# Ethylene_Sensor_Rev2.net
KiCad netlist of a schematic drawn in Altium Designer
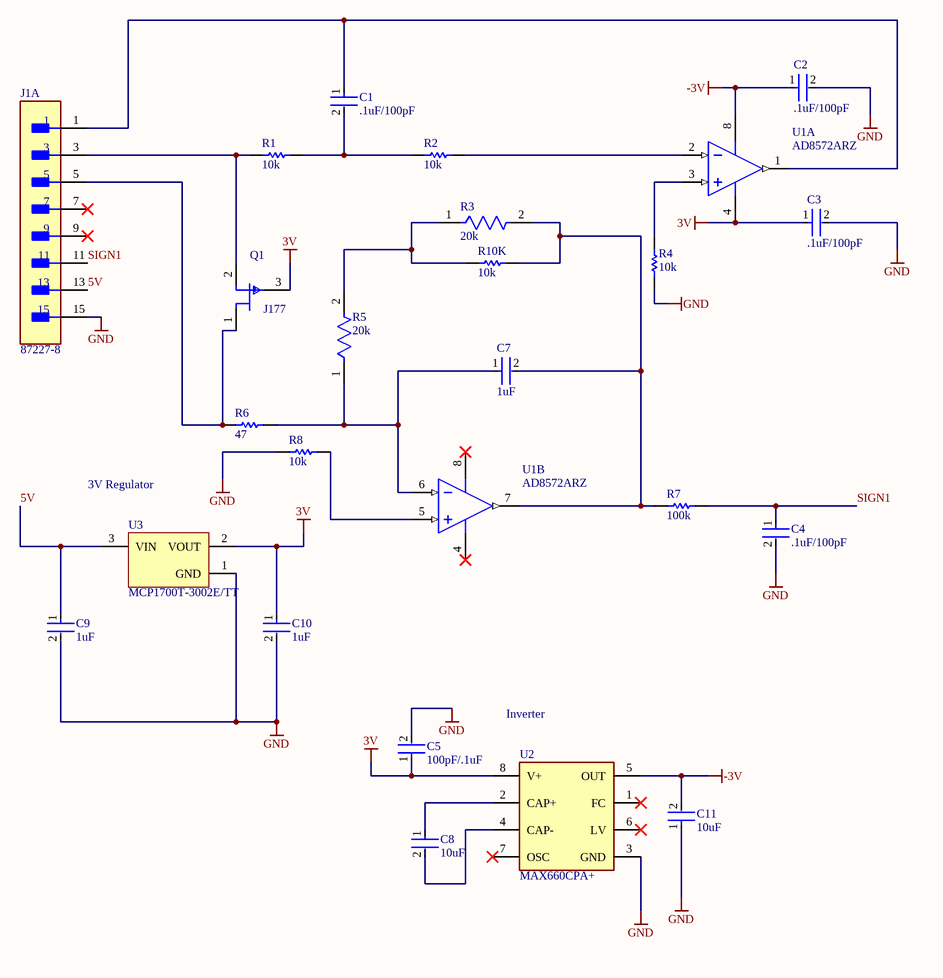
[diagram p0: Ethylene Sensor Rev2.SchDoc]

(export (version "E")
  (design (tool "Eeschema 10.0.6"))
  (components
    (comp (ref "C1")
      (value ".1uF/100pF")
      (footprint "FP-RCE0K1-MFG")
      (description "Cap Ceramic 100pF 100V C0G ±5% Radial 5mm +125°C Automotive Bulk")
      (fields (field (name "TOLERANCE") "5%"))
      (libsource (lib "Altium Content Vault") (part "b4654b650e69147ec39a6b967a45e02"))
    )
    (comp (ref "C2")
      (value ".1uF/100pF")
      (footprint "FP-RCE0K1-MFG")
      (description "Cap Ceramic 100pF 100V C0G ±5% Radial 5mm +125°C Automotive Bulk")
      (fields (field (name "TOLERANCE") "5%"))
      (libsource (lib "Altium Content Vault") (part "b4654b650e69147ec39a6b967a45e02"))
    )
    (comp (ref "C3")
      (value ".1uF/100pF")
      (footprint "FP-RCE0K1-MFG")
      (description "Cap Ceramic 100pF 100V C0G ±5% Radial 5mm +125°C Automotive Bulk")
      (fields (field (name "TOLERANCE") "5%"))
      (libsource (lib "Altium Content Vault") (part "b4654b650e69147ec39a6b967a45e02"))
    )
    (comp (ref "C4")
      (value ".1uF/100pF")
      (footprint "FP-RCE0K1-MFG")
      (description "Cap Ceramic 100pF 100V C0G ±5% Radial 5mm +125°C Automotive Bulk")
      (fields (field (name "TOLERANCE") "5%"))
      (libsource (lib "Altium Content Vault") (part "b4654b650e69147ec39a6b967a45e02"))
    )
    (comp (ref "C5")
      (value "100pF/.1uF")
      (footprint "FP-RCE0DB-MFG")
      (description "Cap Ceramic 100pF 100V C0G ±5% Radial 2.5mm +125°C Ammo Pack")
      (fields (field (name "TOLERANCE") "5%"))
      (libsource (lib "Altium Content Vault") (part "b4654b650e69147ec39a6b967a45e02"))
    )
    (comp (ref "C7")
      (value "1uF")
      (footprint "FP-K105Z20Y5VF5TL2-MFG")
      (description "CAP CER 1UF 50V Y5V RADIAL")
      (fields
        (field (name "TOLERANCE") "-20+80%")
        (field (name "OCTOPART") "https://octopart.com/k105z20y5vf5tl2-vishay-39475252")
      )
      (libsource (lib "Altium Content Vault") (part "11868f565c42a9108669ba33697ecf6"))
    )
    (comp (ref "C8")
      (value "10uF")
      (footprint "FP-RCE3M1-MFG")
      (description "Cap Ceramic 10uF 25V X7R ±10% Radial 5mm +125°C Automotive Ammo Pack")
      (fields (field (name "TOLERANCE") "10%"))
      (libsource (lib "Altium Content Vault") (part "02cd4be3c70576c341d710602a673aa"))
    )
    (comp (ref "C9")
      (value "1uF")
      (footprint "FP-K105Z20Y5VF5TL2-MFG")
      (description "CAP CER 1UF 50V Y5V RADIAL")
      (fields
        (field (name "TOLERANCE") "-20+80%")
        (field (name "OCTOPART") "https://octopart.com/k105z20y5vf5tl2-vishay-39475252")
      )
      (libsource (lib "Altium Content Vault") (part "11868f565c42a9108669ba33697ecf6"))
    )
    (comp (ref "C10")
      (value "1uF")
      (footprint "FP-K105Z20Y5VF5TL2-MFG")
      (description "CAP CER 1UF 50V Y5V RADIAL")
      (fields
        (field (name "TOLERANCE") "-20+80%")
        (field (name "OCTOPART") "https://octopart.com/k105z20y5vf5tl2-vishay-39475252")
      )
      (libsource (lib "Altium Content Vault") (part "11868f565c42a9108669ba33697ecf6"))
    )
    (comp (ref "C11")
      (value "10uF")
      (footprint "FP-RCE3M1-MFG")
      (description "Cap Ceramic 10uF 25V X7R ±10% Radial 5mm +125°C Automotive Ammo Pack")
      (fields (field (name "TOLERANCE") "10%"))
      (libsource (lib "Altium Content Vault") (part "02cd4be3c70576c341d710602a673aa"))
    )
    (comp (ref "J1")
      (value "87227-8")
      (footprint "FP-87227-8-MFG")
      (description "CONN HEADER VERT 16POS 2.54MM")
      (fields
        (field (name "MANUFACTURER") "TE Connectivity")
        (field (name "OCTOPART") "https://octopart.com/87227-8-te+connectivity-39407754")
      )
      (libsource (lib "Altium Content Vault") (part "4b6d22b45e2f925f038cba5d936fbcc"))
    )
    (comp (ref "Q1")
      (value "J177")
      (footprint "FP-318-08-IPC_C")
      (description "JFET P-CH 30V 0.225W SOT23")
      (libsource (lib "Altium Content Vault") (part "f35b6042eff1b6cb0a0a26375b7670e"))
    )
    (comp (ref "R1")
      (value "10k")
      (footprint "OMTE-RES7X2.5-2")
      (fields
        (field (name "TOLERANCE") "±5%")
        (field (name "PARTNUMBER") "OD103JE")
        (field (name "MANUFACTURER") "Ohmite")
      )
      (libsource (lib "Altium Content Vault") (part "RES-2"))
    )
    (comp (ref "R2")
      (value "10k")
      (footprint "OMTE-RES7X2.5-2")
      (fields
        (field (name "TOLERANCE") "±5%")
        (field (name "PARTNUMBER") "OD103JE")
        (field (name "MANUFACTURER") "Ohmite")
      )
      (libsource (lib "Altium Content Vault") (part "RES-2"))
    )
    (comp (ref "R3")
      (value "20k")
      (footprint "FP-S102K-MFG")
      (description "RES 20K OHM 0.6W 0.01% RADIAL")
      (fields (field (name "TOLERANCE") "0.01%"))
      (libsource (lib "Altium Content Vault") (part "1029c3af85768c4190bb7ad29bc67b5"))
    )
    (comp (ref "R4")
      (value "10k")
      (footprint "OMTE-RES7X2.5-2")
      (fields
        (field (name "TOLERANCE") "±5%")
        (field (name "PARTNUMBER") "OD103JE")
        (field (name "MANUFACTURER") "Ohmite")
      )
      (libsource (lib "Altium Content Vault") (part "RES-2"))
    )
    (comp (ref "R5")
      (value "20k")
      (footprint "FP-S102K-MFG")
      (description "RES 20K OHM 0.6W 0.01% RADIAL")
      (fields (field (name "TOLERANCE") "0.01%"))
      (libsource (lib "Altium Content Vault") (part "1029c3af85768c4190bb7ad29bc67b5"))
    )
    (comp (ref "R6")
      (value "47")
      (footprint "RESC1609X50X30LL10T20")
      (fields (field (name "MANUFACTURER") "Vishay Dale") (field (name "PART NUMBER") "CRCW060347R0FKEA"))
      (libsource (lib "Altium Content Vault") (part "RES"))
    )
    (comp (ref "R7")
      (value "100k")
      (footprint "RESA60-630X240")
      (description "Axial Resistor, 100 KOhm, +/- 1%, 0.25 W, -55 to 155 degC, 2-Pin THD, RoHS, Bulk")
      (fields (field (name "TOLERANCE") "1%"))
      (libsource (lib "Altium Content Vault") (part "RES-2"))
    )
    (comp (ref "R8")
      (value "10k")
      (footprint "OMTE-RES7X2.5-2")
      (fields
        (field (name "TOLERANCE") "±5%")
        (field (name "PARTNUMBER") "OD103JE")
        (field (name "MANUFACTURER") "Ohmite")
      )
      (libsource (lib "Altium Content Vault") (part "RES-2"))
    )
    (comp (ref "R10K")
      (value "10k")
      (footprint "OMTE-RES7X2.5-2")
      (fields
        (field (name "TOLERANCE") "±5%")
        (field (name "PARTNUMBER") "OD103JE")
        (field (name "MANUFACTURER") "Ohmite")
      )
      (libsource (lib "Altium Content Vault") (part "RES-2"))
    )
    (comp (ref "U1")
      (value "AD8572ARZ")
      (footprint "ADI-R-8_L")
      (fields (field (name "MANUFACTURER") "Analog Devices") (field (name "GENERIC PART NUMBER") "AD8572"))
      (libsource (lib "Altium Content Vault") (part "ADI-OP29X-R-8"))
    )
    (comp (ref "U2")
      (value "MAX660CPA+")
      (footprint "FP-P8-2-MFG")
      (description "IC REG CHARG PUMP INV 100MA 8DIP")
      (fields
        (field (name "OCTOPART") "https://octopart.com/max660cpa%2B-maxim+integrated-39427913")
        (field (name "MANUFACTURER") "Maxim Integrated")
      )
      (libsource (lib "Altium Content Vault") (part "cb4f88f8f8861f0afe4fdc40404f196"))
    )
    (comp (ref "U3")
      (value "MCP1700T-3002E/TT")
      (footprint "SOT-23-TT3_L")
      (description "Low Quiescent Current LDO, 3-Pin SOT-23, Extended Temperature, Tape and Reel")
      (libsource (lib "Altium Content Vault") (part "PM-LINEREG-MCP1700-IL3"))
    )
  )
  (nets
    (net (code "1") (name "-3V") (class "Default")
      (node (ref "C11") (pin "2") (pinfunction "2_2") (pintype "passive"))
      (node (ref "C2") (pin "1") (pinfunction "1_1") (pintype "passive"))
      (node (ref "U1") (pin "8") (pinfunction "+V_8") (pintype "power_in"))
      (node (ref "U2") (pin "5") (pinfunction "OUT_5") (pintype "power_in"))
    )
    (net (code "2") (name "/5V") (class "Default")
      (node (ref "C9") (pin "1") (pinfunction "1_1") (pintype "passive"))
      (node (ref "J1") (pin "13") (pinfunction "13_13") (pintype "passive"))
      (node (ref "U3") (pin "3") (pinfunction "VIN_3") (pintype "power_in"))
    )
    (net (code "3") (name "/SIGN1") (class "Default")
      (node (ref "C4") (pin "1") (pinfunction "1_1") (pintype "passive"))
      (node (ref "J1") (pin "11") (pinfunction "11_11") (pintype "passive"))
      (node (ref "R7") (pin "2") (pinfunction "2_2") (pintype "passive"))
    )
    (net (code "4") (name "3V") (class "Default")
      (node (ref "C10") (pin "1") (pinfunction "1_1") (pintype "passive"))
      (node (ref "C3") (pin "1") (pinfunction "1_1") (pintype "passive"))
      (node (ref "C5") (pin "1") (pinfunction "1_1") (pintype "passive"))
      (node (ref "Q1") (pin "3") (pinfunction "G_3") (pintype "passive"))
      (node (ref "U1") (pin "4") (pinfunction "-V_4") (pintype "power_in"))
      (node (ref "U2") (pin "8") (pinfunction "V+_8") (pintype "power_in"))
      (node (ref "U3") (pin "2") (pinfunction "VOUT_2") (pintype "power_in"))
    )
    (net (code "5") (name "GND") (class "Default")
      (node (ref "C10") (pin "2") (pinfunction "2_2") (pintype "passive"))
      (node (ref "C11") (pin "1") (pinfunction "1_1") (pintype "passive"))
      (node (ref "C2") (pin "2") (pinfunction "2_2") (pintype "passive"))
      (node (ref "C3") (pin "2") (pinfunction "2_2") (pintype "passive"))
      (node (ref "C4") (pin "2") (pinfunction "2_2") (pintype "passive"))
      (node (ref "C5") (pin "2") (pinfunction "2_2") (pintype "passive"))
      (node (ref "C9") (pin "2") (pinfunction "2_2") (pintype "passive"))
      (node (ref "J1") (pin "15") (pinfunction "15_15") (pintype "passive"))
      (node (ref "R4") (pin "1") (pinfunction "1_1") (pintype "passive"))
      (node (ref "R8") (pin "1") (pinfunction "1_1") (pintype "passive"))
      (node (ref "U2") (pin "3") (pinfunction "GND_3") (pintype "power_in"))
      (node (ref "U3") (pin "1") (pinfunction "GND_1") (pintype "power_in"))
    )
    (net (code "6") (name "Net-(C1-Pad2)") (class "Default")
      (node (ref "C1") (pin "2") (pinfunction "2_2") (pintype "passive"))
      (node (ref "R1") (pin "2") (pinfunction "2_2") (pintype "passive"))
      (node (ref "R2") (pin "1") (pinfunction "1_1") (pintype "passive"))
    )
    (net (code "7") (name "Net-(Q1-D)") (class "Default")
      (node (ref "J1") (pin "5") (pinfunction "5_5") (pintype "passive"))
      (node (ref "Q1") (pin "1") (pinfunction "D_1") (pintype "passive"))
      (node (ref "R6") (pin "1") (pinfunction "1_1") (pintype "passive"))
    )
    (net (code "8") (name "Net-(Q1-S)") (class "Default")
      (node (ref "J1") (pin "3") (pinfunction "3_3") (pintype "passive"))
      (node (ref "Q1") (pin "2") (pinfunction "S_2") (pintype "passive"))
      (node (ref "R1") (pin "1") (pinfunction "1_1") (pintype "passive"))
    )
    (net (code "9") (name "Net-(R10K-Pad1)") (class "Default")
      (node (ref "R10K") (pin "1") (pinfunction "1_1") (pintype "passive"))
      (node (ref "R3") (pin "1") (pinfunction "1_1") (pintype "passive"))
      (node (ref "R5") (pin "2") (pinfunction "2_2") (pintype "passive"))
    )
    (net (code "10") (name "Net-(U1A-+IN_A)") (class "Default")
      (node (ref "R4") (pin "2") (pinfunction "2_2") (pintype "passive"))
      (node (ref "U1") (pin "3") (pinfunction "+IN_A_3") (pintype "input"))
    )
    (net (code "11") (name "Net-(U1A--IN_A)") (class "Default")
      (node (ref "R2") (pin "2") (pinfunction "2_2") (pintype "passive"))
      (node (ref "U1") (pin "2") (pinfunction "-IN_A_2") (pintype "input"))
    )
    (net (code "12") (name "Net-(U1A-OUT_A)") (class "Default")
      (node (ref "C1") (pin "1") (pinfunction "1_1") (pintype "passive"))
      (node (ref "J1") (pin "1") (pinfunction "1_1") (pintype "passive"))
      (node (ref "U1") (pin "1") (pinfunction "OUT_A_1") (pintype "output"))
    )
    (net (code "13") (name "Net-(U1B-+IN_B)") (class "Default")
      (node (ref "R8") (pin "2") (pinfunction "2_2") (pintype "passive"))
      (node (ref "U1") (pin "5") (pinfunction "+IN_B_5") (pintype "input"))
    )
    (net (code "14") (name "Net-(U1B--IN_B)") (class "Default")
      (node (ref "C7") (pin "1") (pinfunction "1_1") (pintype "passive"))
      (node (ref "R5") (pin "1") (pinfunction "1_1") (pintype "passive"))
      (node (ref "R6") (pin "2") (pinfunction "2_2") (pintype "passive"))
      (node (ref "U1") (pin "6") (pinfunction "-IN_B_6") (pintype "input"))
    )
    (net (code "15") (name "Net-(U1B-OUT_B)") (class "Default")
      (node (ref "C7") (pin "2") (pinfunction "2_2") (pintype "passive"))
      (node (ref "R10K") (pin "2") (pinfunction "2_2") (pintype "passive"))
      (node (ref "R3") (pin "2") (pinfunction "2_2") (pintype "passive"))
      (node (ref "R7") (pin "1") (pinfunction "1_1") (pintype "passive"))
      (node (ref "U1") (pin "7") (pinfunction "OUT_B_7") (pintype "output"))
    )
    (net (code "16") (name "Net-(U2-CAP+)") (class "Default")
      (node (ref "C8") (pin "1") (pinfunction "1_1") (pintype "passive"))
      (node (ref "U2") (pin "2") (pinfunction "CAP+_2") (pintype "passive"))
    )
    (net (code "17") (name "Net-(U2-CAP-)") (class "Default")
      (node (ref "C8") (pin "2") (pinfunction "2_2") (pintype "passive"))
      (node (ref "U2") (pin "4") (pinfunction "CAP-_4") (pintype "passive"))
    )
    (net (code "18") (name "unconnected-(J1-Pad7)") (class "Default")
      (node (ref "J1") (pin "7") (pinfunction "7_7") (pintype "passive+no_connect"))
    )
    (net (code "19") (name "unconnected-(J1-Pad9)") (class "Default")
      (node (ref "J1") (pin "9") (pinfunction "9_9") (pintype "passive+no_connect"))
    )
    (net (code "20") (name "unconnected-(U1B-+V-Pad8)") (class "Default")
      (node (ref "U1") (pin "8") (pinfunction "+V_8") (pintype "power_in+no_connect"))
    )
    (net (code "21") (name "unconnected-(U1B--V-Pad4)") (class "Default")
      (node (ref "U1") (pin "4") (pinfunction "-V_4") (pintype "power_in+no_connect"))
    )
    (net (code "22") (name "unconnected-(U2-FC-Pad1)") (class "Default")
      (node (ref "U2") (pin "1") (pinfunction "FC_1") (pintype "passive+no_connect"))
    )
    (net (code "23") (name "unconnected-(U2-LV-Pad6)") (class "Default")
      (node (ref "U2") (pin "6") (pinfunction "LV_6") (pintype "passive+no_connect"))
    )
    (net (code "24") (name "unconnected-(U2-OSC-Pad7)") (class "Default")
      (node (ref "U2") (pin "7") (pinfunction "OSC_7") (pintype "passive+no_connect"))
    )
  )
)
